# Microcontroller_board_Photodiode_plate.net
KiCad netlist of a schematic drawn in EasyEDA
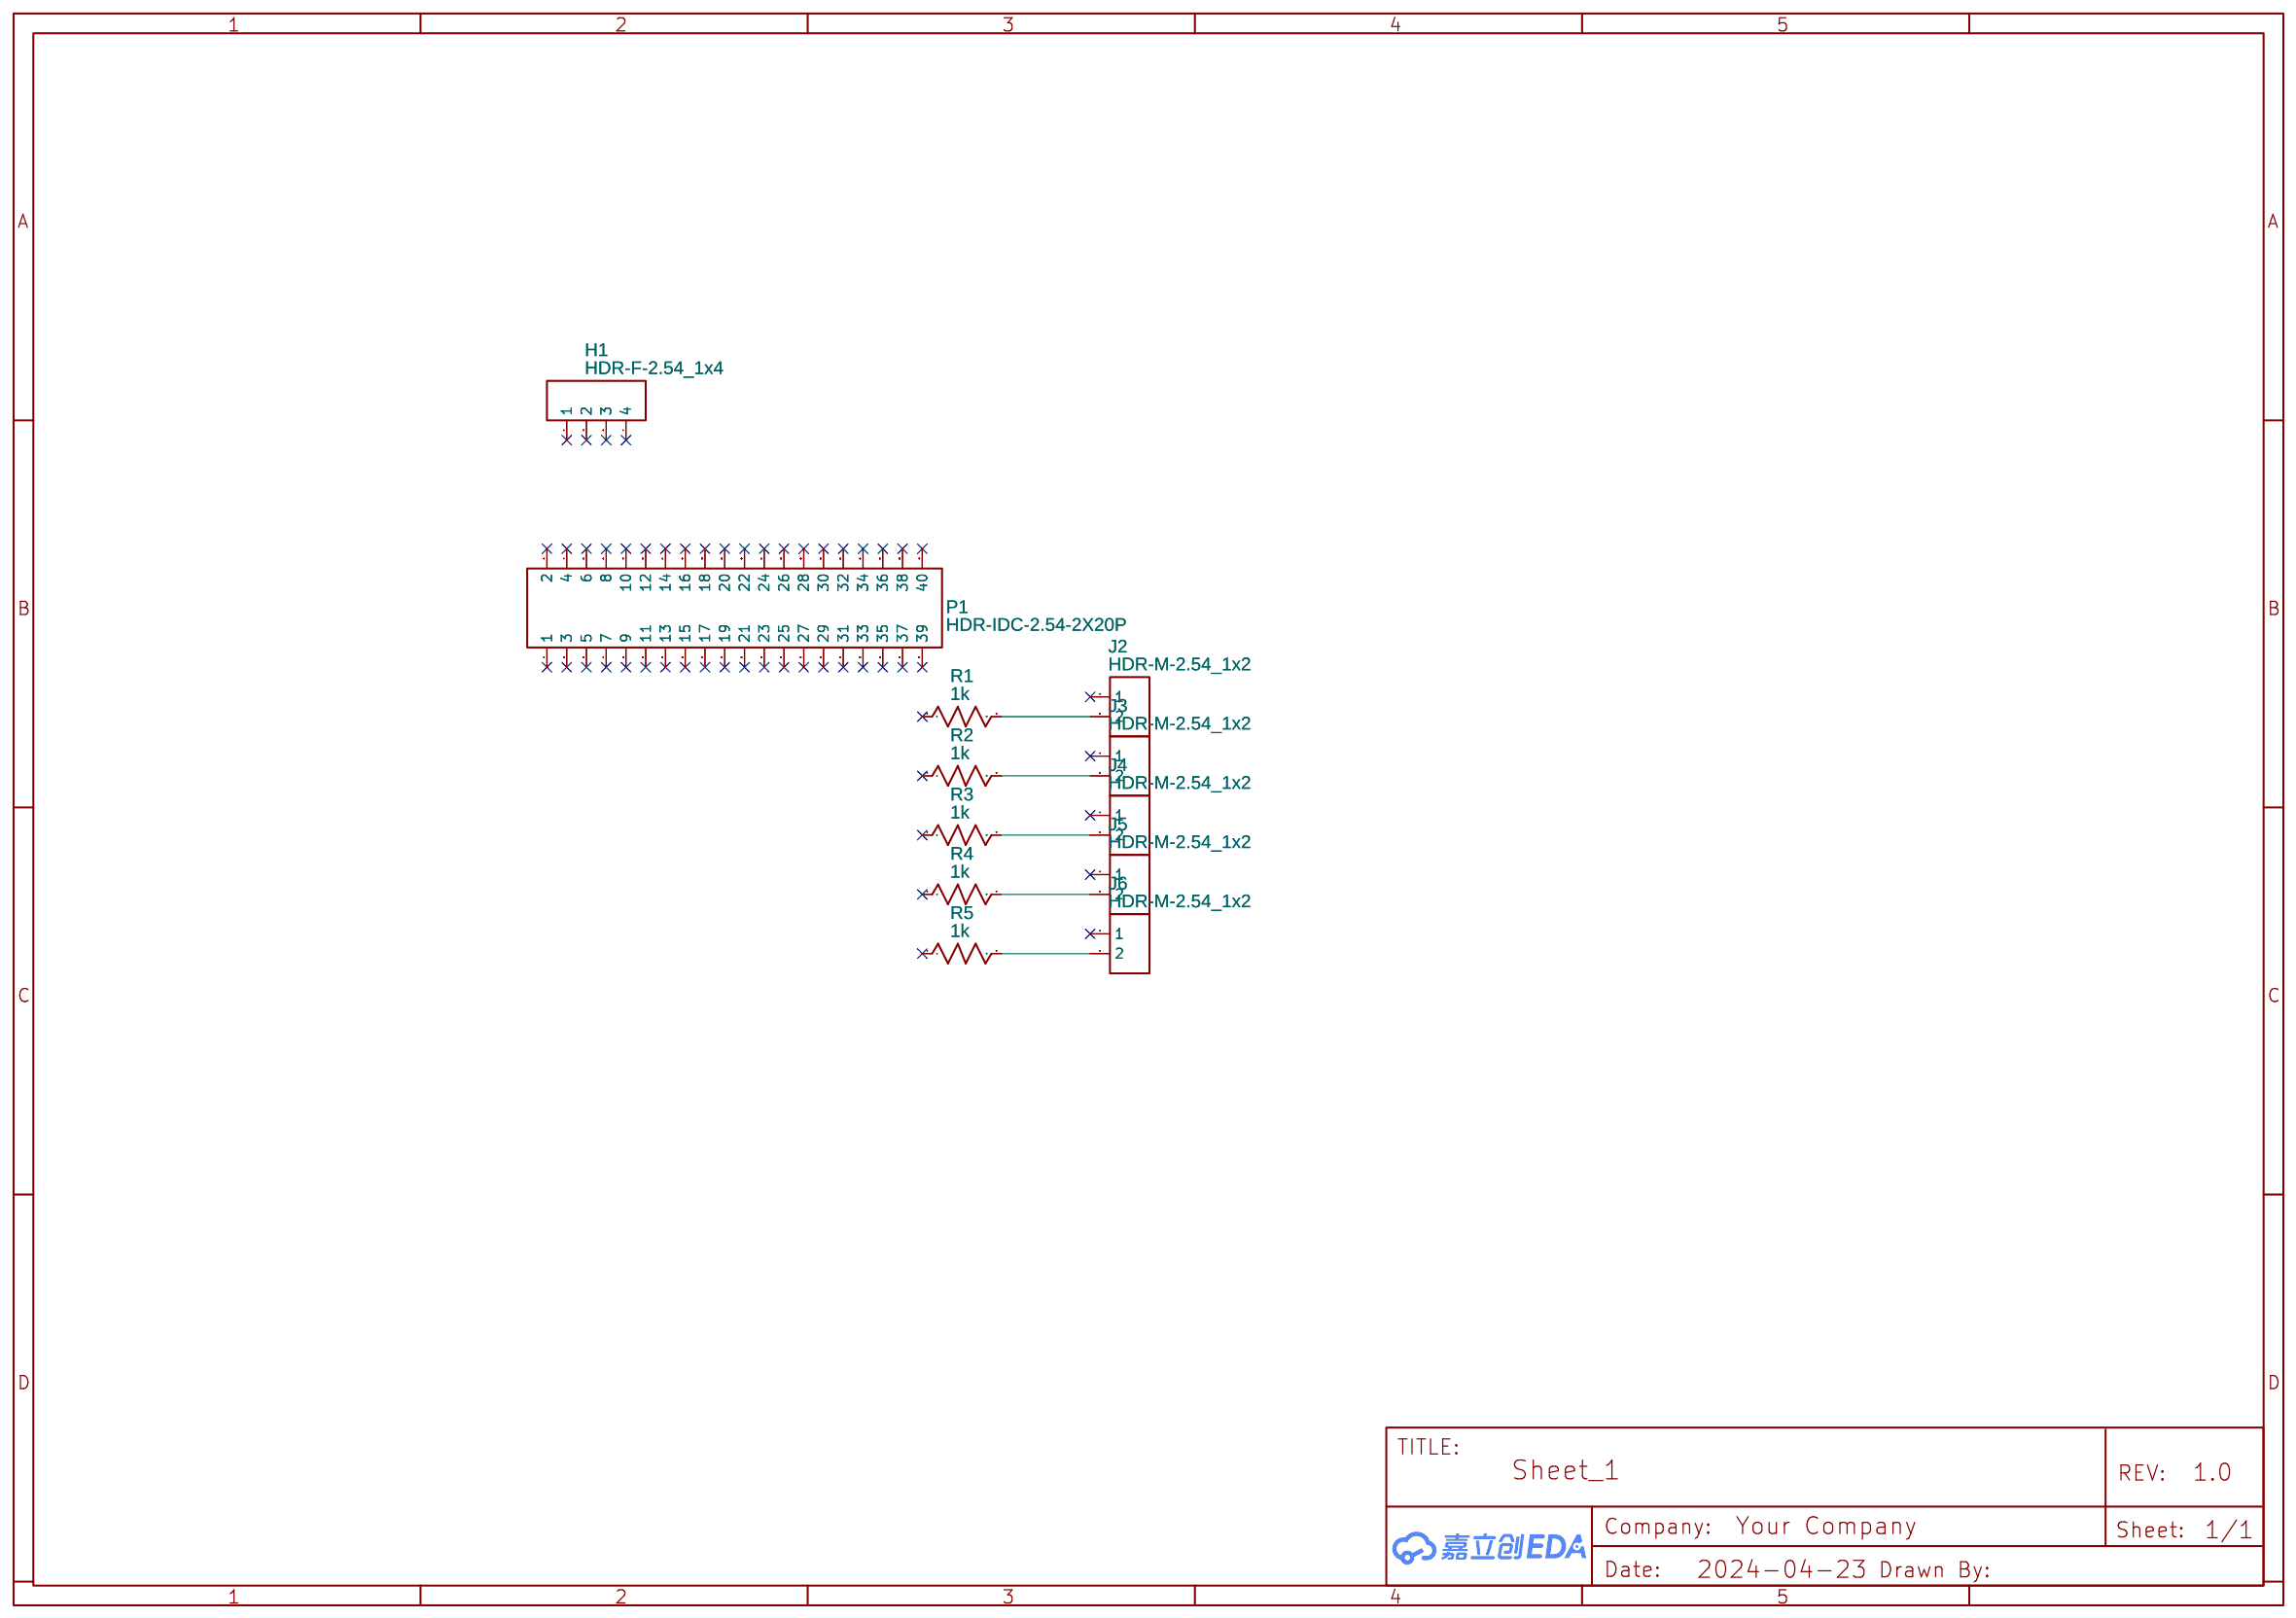
[diagram p0: schematic sheet]

(export (version "E")
  (design (tool "Eeschema 10.0.6"))
  (components
    (comp (ref "H1")
      (value "HDR-F-2.54_1x4")
      (fields (field (name "BOM_Supplier Part") "C225501"))
      (libsource (lib "") (part "HDR-F-2.54_1x4"))
    )
    (comp (ref "J2")
      (value "HDR-M-2.54_1x2")
      (fields (field (name "BOM_Supplier Part") "C124375"))
      (libsource (lib "") (part "HDR-M-2.54_1x2"))
    )
    (comp (ref "J3")
      (value "HDR-M-2.54_1x2")
      (fields (field (name "BOM_Supplier Part") "C124375"))
      (libsource (lib "") (part "HDR-M-2.54_1x2"))
    )
    (comp (ref "J4")
      (value "HDR-M-2.54_1x2")
      (fields (field (name "BOM_Supplier Part") "C124375"))
      (libsource (lib "") (part "HDR-M-2.54_1x2"))
    )
    (comp (ref "J5")
      (value "HDR-M-2.54_1x2")
      (fields (field (name "BOM_Supplier Part") "C124375"))
      (libsource (lib "") (part "HDR-M-2.54_1x2"))
    )
    (comp (ref "J6")
      (value "HDR-M-2.54_1x2")
      (fields (field (name "BOM_Supplier Part") "C124375"))
      (libsource (lib "") (part "HDR-M-2.54_1x2"))
    )
    (comp (ref "P1")
      (value "HDR-IDC-2.54-2X20P")
      (fields
        (field (name "BOM_Manufacturer Part") "IDC Box 2X20 2.54MM")
        (field (name "BOM_Supplier Part") "C9138")
      )
      (libsource (lib "") (part "HDR-IDC-2.54-2X20P"))
    )
    (comp (ref "R1") (value "1k") (libsource (lib "") (part "R_AXIAL-0.3_US")))
    (comp (ref "R2") (value "1k") (libsource (lib "") (part "R_AXIAL-0.3_US")))
    (comp (ref "R3") (value "1k") (libsource (lib "") (part "R_AXIAL-0.3_US")))
    (comp (ref "R4") (value "1k") (libsource (lib "") (part "R_AXIAL-0.3_US")))
    (comp (ref "R5") (value "1k") (libsource (lib "") (part "R_AXIAL-0.3_US")))
  )
  (nets
    (net (code "1") (name "Net-(J2-Pad2)") (class "Default")
      (node (ref "J2") (pin "2") (pinfunction "2_2") (pintype "unspecified"))
      (node (ref "R1") (pin "2") (pinfunction "2_2") (pintype "unspecified"))
    )
    (net (code "2") (name "Net-(J3-Pad2)") (class "Default")
      (node (ref "J3") (pin "2") (pinfunction "2_2") (pintype "unspecified"))
      (node (ref "R2") (pin "2") (pinfunction "2_2") (pintype "unspecified"))
    )
    (net (code "3") (name "Net-(J4-Pad2)") (class "Default")
      (node (ref "J4") (pin "2") (pinfunction "2_2") (pintype "unspecified"))
      (node (ref "R3") (pin "2") (pinfunction "2_2") (pintype "unspecified"))
    )
    (net (code "4") (name "Net-(J5-Pad2)") (class "Default")
      (node (ref "J5") (pin "2") (pinfunction "2_2") (pintype "unspecified"))
      (node (ref "R4") (pin "2") (pinfunction "2_2") (pintype "unspecified"))
    )
    (net (code "5") (name "Net-(J6-Pad2)") (class "Default")
      (node (ref "J6") (pin "2") (pinfunction "2_2") (pintype "unspecified"))
      (node (ref "R5") (pin "2") (pinfunction "2_2") (pintype "unspecified"))
    )
    (net (code "6") (name "unconnected-(H1-Pad1)") (class "Default")
      (node (ref "H1") (pin "1") (pinfunction "1_1") (pintype "unspecified+no_connect"))
    )
    (net (code "7") (name "unconnected-(H1-Pad2)") (class "Default")
      (node (ref "H1") (pin "2") (pinfunction "2_2") (pintype "unspecified+no_connect"))
    )
    (net (code "8") (name "unconnected-(H1-Pad3)") (class "Default")
      (node (ref "H1") (pin "3") (pinfunction "3_3") (pintype "unspecified+no_connect"))
    )
    (net (code "9") (name "unconnected-(H1-Pad4)") (class "Default")
      (node (ref "H1") (pin "4") (pinfunction "4_4") (pintype "unspecified+no_connect"))
    )
    (net (code "10") (name "unconnected-(J2-Pad1)") (class "Default")
      (node (ref "J2") (pin "1") (pinfunction "1_1") (pintype "unspecified+no_connect"))
    )
    (net (code "11") (name "unconnected-(J3-Pad1)") (class "Default")
      (node (ref "J3") (pin "1") (pinfunction "1_1") (pintype "unspecified+no_connect"))
    )
    (net (code "12") (name "unconnected-(J4-Pad1)") (class "Default")
      (node (ref "J4") (pin "1") (pinfunction "1_1") (pintype "unspecified+no_connect"))
    )
    (net (code "13") (name "unconnected-(J5-Pad1)") (class "Default")
      (node (ref "J5") (pin "1") (pinfunction "1_1") (pintype "unspecified+no_connect"))
    )
    (net (code "14") (name "unconnected-(J6-Pad1)") (class "Default")
      (node (ref "J6") (pin "1") (pinfunction "1_1") (pintype "unspecified+no_connect"))
    )
    (net (code "15") (name "unconnected-(P1-Pad1)") (class "Default")
      (node (ref "P1") (pin "1") (pinfunction "1_1") (pintype "unspecified+no_connect"))
    )
    (net (code "16") (name "unconnected-(P1-Pad2)") (class "Default")
      (node (ref "P1") (pin "2") (pinfunction "2_2") (pintype "unspecified+no_connect"))
    )
    (net (code "17") (name "unconnected-(P1-Pad3)") (class "Default")
      (node (ref "P1") (pin "3") (pinfunction "3_3") (pintype "unspecified+no_connect"))
    )
    (net (code "18") (name "unconnected-(P1-Pad4)") (class "Default")
      (node (ref "P1") (pin "4") (pinfunction "4_4") (pintype "unspecified+no_connect"))
    )
    (net (code "19") (name "unconnected-(P1-Pad5)") (class "Default")
      (node (ref "P1") (pin "5") (pinfunction "5_5") (pintype "unspecified+no_connect"))
    )
    (net (code "20") (name "unconnected-(P1-Pad6)") (class "Default")
      (node (ref "P1") (pin "6") (pinfunction "6_6") (pintype "unspecified+no_connect"))
    )
    (net (code "21") (name "unconnected-(P1-Pad7)") (class "Default")
      (node (ref "P1") (pin "7") (pinfunction "7_7") (pintype "unspecified+no_connect"))
    )
    (net (code "22") (name "unconnected-(P1-Pad8)") (class "Default")
      (node (ref "P1") (pin "8") (pinfunction "8_8") (pintype "unspecified+no_connect"))
    )
    (net (code "23") (name "unconnected-(P1-Pad9)") (class "Default")
      (node (ref "P1") (pin "9") (pinfunction "9_9") (pintype "unspecified+no_connect"))
    )
    (net (code "24") (name "unconnected-(P1-Pad10)") (class "Default")
      (node (ref "P1") (pin "10") (pinfunction "10_10") (pintype "unspecified+no_connect"))
    )
    (net (code "25") (name "unconnected-(P1-Pad11)") (class "Default")
      (node (ref "P1") (pin "11") (pinfunction "11_11") (pintype "unspecified+no_connect"))
    )
    (net (code "26") (name "unconnected-(P1-Pad12)") (class "Default")
      (node (ref "P1") (pin "12") (pinfunction "12_12") (pintype "unspecified+no_connect"))
    )
    (net (code "27") (name "unconnected-(P1-Pad13)") (class "Default")
      (node (ref "P1") (pin "13") (pinfunction "13_13") (pintype "unspecified+no_connect"))
    )
    (net (code "28") (name "unconnected-(P1-Pad14)") (class "Default")
      (node (ref "P1") (pin "14") (pinfunction "14_14") (pintype "unspecified+no_connect"))
    )
    (net (code "29") (name "unconnected-(P1-Pad15)") (class "Default")
      (node (ref "P1") (pin "15") (pinfunction "15_15") (pintype "unspecified+no_connect"))
    )
    (net (code "30") (name "unconnected-(P1-Pad16)") (class "Default")
      (node (ref "P1") (pin "16") (pinfunction "16_16") (pintype "unspecified+no_connect"))
    )
    (net (code "31") (name "unconnected-(P1-Pad17)") (class "Default")
      (node (ref "P1") (pin "17") (pinfunction "17_17") (pintype "unspecified+no_connect"))
    )
    (net (code "32") (name "unconnected-(P1-Pad18)") (class "Default")
      (node (ref "P1") (pin "18") (pinfunction "18_18") (pintype "unspecified+no_connect"))
    )
    (net (code "33") (name "unconnected-(P1-Pad19)") (class "Default")
      (node (ref "P1") (pin "19") (pinfunction "19_19") (pintype "unspecified+no_connect"))
    )
    (net (code "34") (name "unconnected-(P1-Pad20)") (class "Default")
      (node (ref "P1") (pin "20") (pinfunction "20_20") (pintype "unspecified+no_connect"))
    )
    (net (code "35") (name "unconnected-(P1-Pad21)") (class "Default")
      (node (ref "P1") (pin "21") (pinfunction "21_21") (pintype "unspecified+no_connect"))
    )
    (net (code "36") (name "unconnected-(P1-Pad22)") (class "Default")
      (node (ref "P1") (pin "22") (pinfunction "22_22") (pintype "unspecified+no_connect"))
    )
    (net (code "37") (name "unconnected-(P1-Pad23)") (class "Default")
      (node (ref "P1") (pin "23") (pinfunction "23_23") (pintype "unspecified+no_connect"))
    )
    (net (code "38") (name "unconnected-(P1-Pad24)") (class "Default")
      (node (ref "P1") (pin "24") (pinfunction "24_24") (pintype "unspecified+no_connect"))
    )
    (net (code "39") (name "unconnected-(P1-Pad25)") (class "Default")
      (node (ref "P1") (pin "25") (pinfunction "25_25") (pintype "unspecified+no_connect"))
    )
    (net (code "40") (name "unconnected-(P1-Pad26)") (class "Default")
      (node (ref "P1") (pin "26") (pinfunction "26_26") (pintype "unspecified+no_connect"))
    )
    (net (code "41") (name "unconnected-(P1-Pad27)") (class "Default")
      (node (ref "P1") (pin "27") (pinfunction "27_27") (pintype "unspecified+no_connect"))
    )
    (net (code "42") (name "unconnected-(P1-Pad28)") (class "Default")
      (node (ref "P1") (pin "28") (pinfunction "28_28") (pintype "unspecified+no_connect"))
    )
    (net (code "43") (name "unconnected-(P1-Pad29)") (class "Default")
      (node (ref "P1") (pin "29") (pinfunction "29_29") (pintype "unspecified+no_connect"))
    )
    (net (code "44") (name "unconnected-(P1-Pad30)") (class "Default")
      (node (ref "P1") (pin "30") (pinfunction "30_30") (pintype "unspecified+no_connect"))
    )
    (net (code "45") (name "unconnected-(P1-Pad31)") (class "Default")
      (node (ref "P1") (pin "31") (pinfunction "31_31") (pintype "unspecified+no_connect"))
    )
    (net (code "46") (name "unconnected-(P1-Pad32)") (class "Default")
      (node (ref "P1") (pin "32") (pinfunction "32_32") (pintype "unspecified+no_connect"))
    )
    (net (code "47") (name "unconnected-(P1-Pad33)") (class "Default")
      (node (ref "P1") (pin "33") (pinfunction "33_33") (pintype "unspecified+no_connect"))
    )
    (net (code "48") (name "unconnected-(P1-Pad34)") (class "Default")
      (node (ref "P1") (pin "34") (pinfunction "34_34") (pintype "unspecified+no_connect"))
    )
    (net (code "49") (name "unconnected-(P1-Pad35)") (class "Default")
      (node (ref "P1") (pin "35") (pinfunction "35_35") (pintype "unspecified+no_connect"))
    )
    (net (code "50") (name "unconnected-(P1-Pad36)") (class "Default")
      (node (ref "P1") (pin "36") (pinfunction "36_36") (pintype "unspecified+no_connect"))
    )
    (net (code "51") (name "unconnected-(P1-Pad37)") (class "Default")
      (node (ref "P1") (pin "37") (pinfunction "37_37") (pintype "unspecified+no_connect"))
    )
    (net (code "52") (name "unconnected-(P1-Pad38)") (class "Default")
      (node (ref "P1") (pin "38") (pinfunction "38_38") (pintype "unspecified+no_connect"))
    )
    (net (code "53") (name "unconnected-(P1-Pad39)") (class "Default")
      (node (ref "P1") (pin "39") (pinfunction "39_39") (pintype "unspecified+no_connect"))
    )
    (net (code "54") (name "unconnected-(P1-Pad40)") (class "Default")
      (node (ref "P1") (pin "40") (pinfunction "40_40") (pintype "unspecified+no_connect"))
    )
    (net (code "55") (name "unconnected-(R1-Pad1)") (class "Default")
      (node (ref "R1") (pin "1") (pinfunction "1_1") (pintype "unspecified+no_connect"))
    )
    (net (code "56") (name "unconnected-(R2-Pad1)") (class "Default")
      (node (ref "R2") (pin "1") (pinfunction "1_1") (pintype "unspecified+no_connect"))
    )
    (net (code "57") (name "unconnected-(R3-Pad1)") (class "Default")
      (node (ref "R3") (pin "1") (pinfunction "1_1") (pintype "unspecified+no_connect"))
    )
    (net (code "58") (name "unconnected-(R4-Pad1)") (class "Default")
      (node (ref "R4") (pin "1") (pinfunction "1_1") (pintype "unspecified+no_connect"))
    )
    (net (code "59") (name "unconnected-(R5-Pad1)") (class "Default")
      (node (ref "R5") (pin "1") (pinfunction "1_1") (pintype "unspecified+no_connect"))
    )
  )
)
